# sbus-inverter-pro-micro.net
KiCad netlist of a schematic drawn in EAGLE
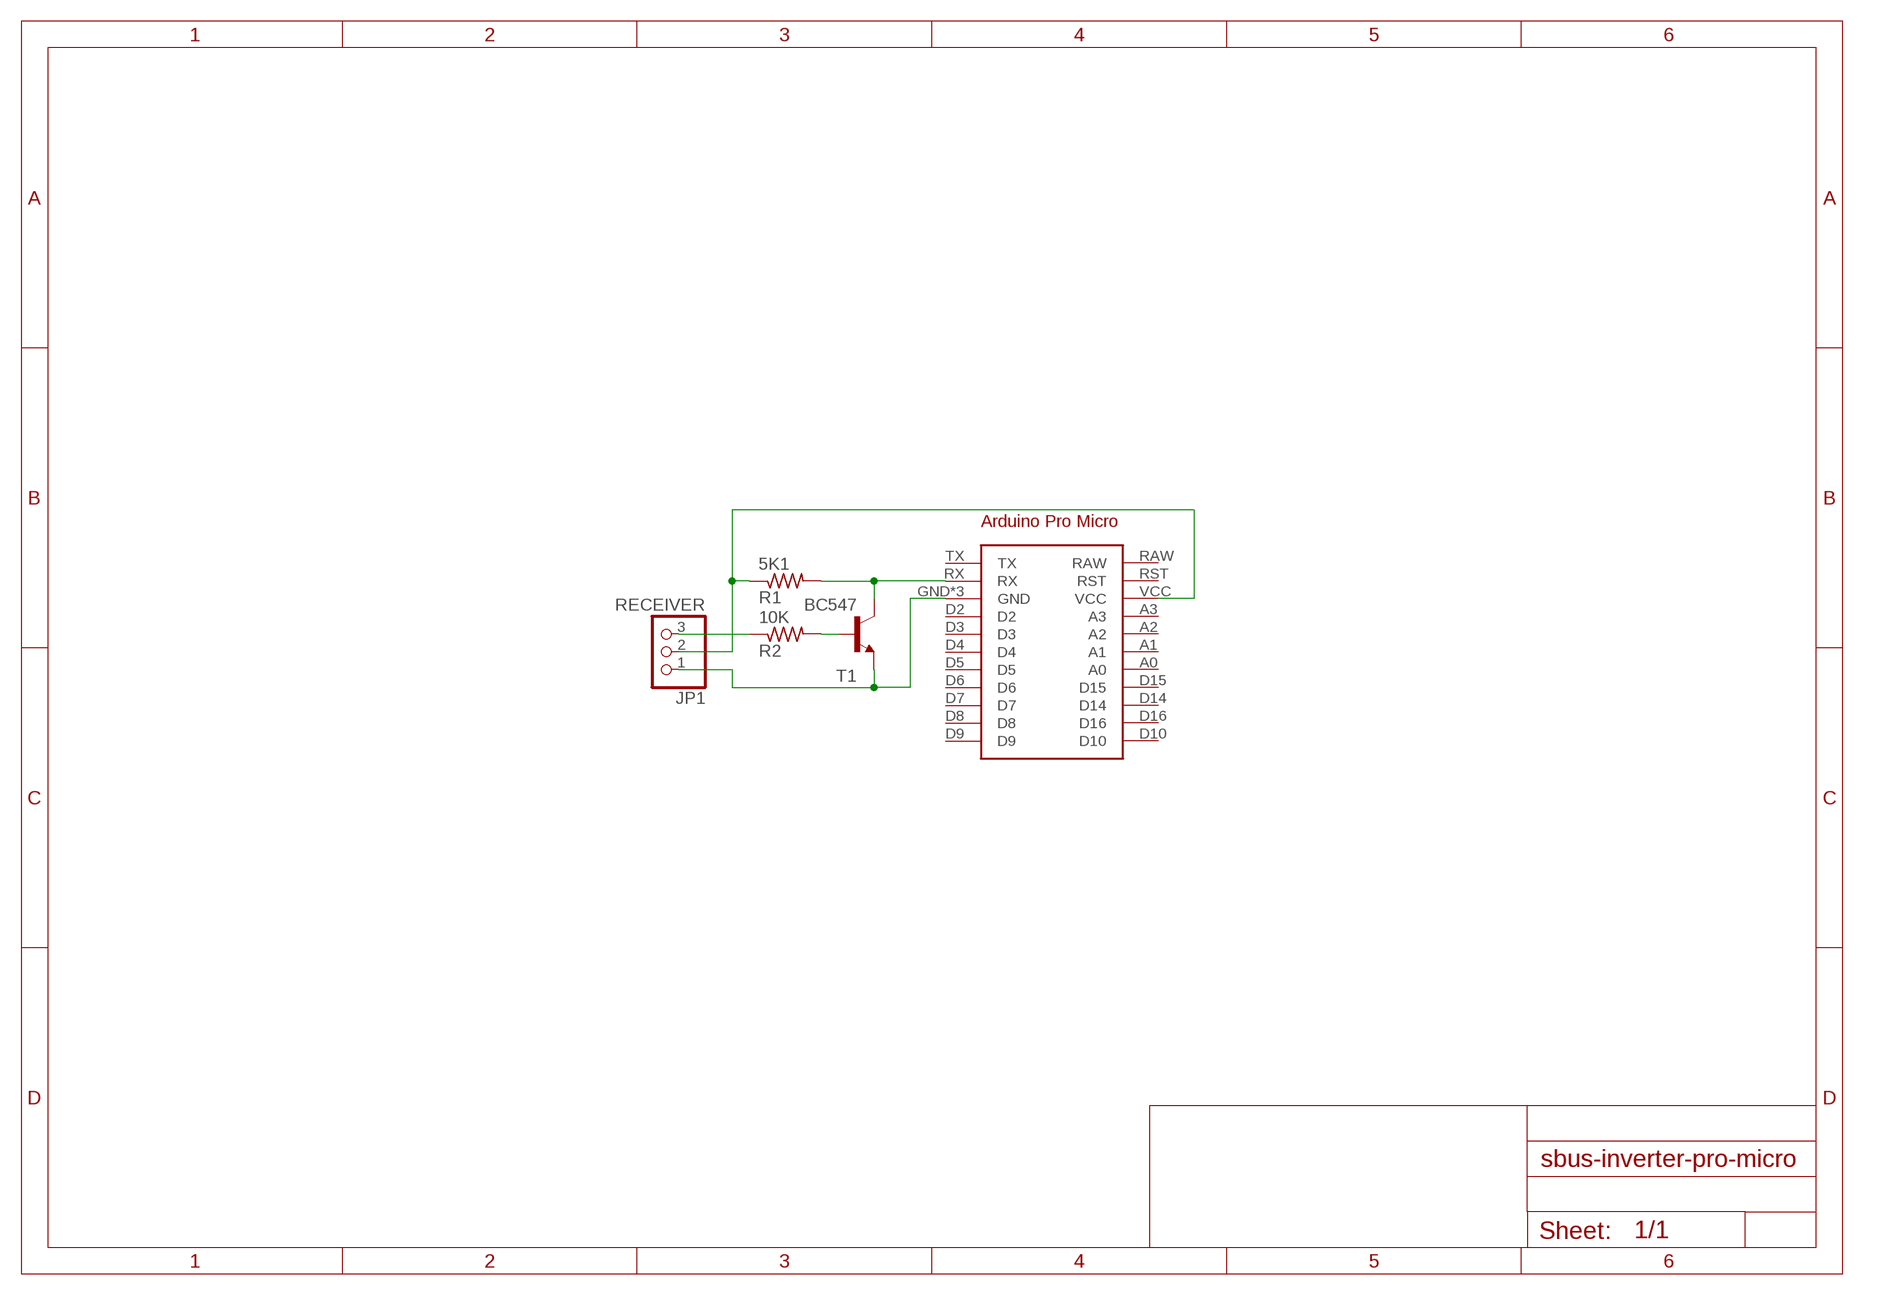
[diagram p0: schematic, sheet 1]

(export (version "E")
  (design (tool "Eeschema 10.0.6"))
  (components
    (comp (ref "ARDUINO1")
      (value "ARDUINO_PRO_MICRO")
      (footprint "eagle-import:ARDUINO_PRO_MICRO")
      (libsource (lib "eagle-import") (part "ARDUINO_PRO_MICRO"))
    )
    (comp (ref "JP1")
      (value "RECEIVER")
      (footprint "eagle-import:1X03_90")
      (libsource (lib "eagle-import") (part "PINHD-1X3/90"))
    )
    (comp (ref "R1")
      (value "5K1")
      (footprint "eagle-import:0207_10")
      (libsource (lib "eagle-import") (part "R-US_0207/10"))
    )
    (comp (ref "R2")
      (value "10K")
      (footprint "eagle-import:0207_10")
      (libsource (lib "eagle-import") (part "R-US_0207/10"))
    )
    (comp (ref "T1")
      (value "BC547")
      (footprint "eagle-import:TO92")
      (libsource (lib "eagle-import") (part "BC547"))
    )
  )
  (nets
    (net (code "1") (name "Net-(ARDUINO1-PadVCC)") (class "Default")
      (node (ref "ARDUINO1") (pin "VCC") (pinfunction "VCC_VCC") (pintype "power_in"))
      (node (ref "JP1") (pin "2") (pinfunction "2_2") (pintype "passive"))
      (node (ref "R1") (pin "1") (pinfunction "1_1") (pintype "passive"))
    )
    (net (code "2") (name "Net-(JP1-Pad3)") (class "Default")
      (node (ref "JP1") (pin "3") (pinfunction "3_3") (pintype "passive"))
      (node (ref "R2") (pin "1") (pinfunction "1_1") (pintype "passive"))
    )
    (net (code "3") (name "Net-(T1-B)") (class "Default")
      (node (ref "R2") (pin "2") (pinfunction "2_2") (pintype "passive"))
      (node (ref "T1") (pin "2") (pinfunction "B_2") (pintype "passive"))
    )
    (net (code "4") (name "Net-(T1-C)") (class "Default")
      (node (ref "ARDUINO1") (pin "RX") (pinfunction "RX_RX") (pintype "bidirectional"))
      (node (ref "R1") (pin "2") (pinfunction "2_2") (pintype "passive"))
      (node (ref "T1") (pin "3") (pinfunction "C_3") (pintype "passive"))
    )
    (net (code "5") (name "Net-(T1-E)") (class "Default")
      (node (ref "ARDUINO1") (pin "GND") (pinfunction "GND_GND") (pintype "power_in"))
      (node (ref "ARDUINO1") (pin "GND@1") (pinfunction "GND_GND@1") (pintype "power_in"))
      (node (ref "ARDUINO1") (pin "GND@2") (pinfunction "GND_GND@2") (pintype "power_in"))
      (node (ref "JP1") (pin "1") (pinfunction "1_1") (pintype "passive"))
      (node (ref "T1") (pin "1") (pinfunction "E_1") (pintype "passive"))
    )
    (net (code "6") (name "unconnected-(ARDUINO1-PadA0)") (class "Default")
      (node (ref "ARDUINO1") (pin "A0") (pinfunction "A0_A0") (pintype "bidirectional"))
    )
    (net (code "7") (name "unconnected-(ARDUINO1-PadA1)") (class "Default")
      (node (ref "ARDUINO1") (pin "A1") (pinfunction "A1_A1") (pintype "bidirectional"))
    )
    (net (code "8") (name "unconnected-(ARDUINO1-PadA2)") (class "Default")
      (node (ref "ARDUINO1") (pin "A2") (pinfunction "A2_A2") (pintype "bidirectional"))
    )
    (net (code "9") (name "unconnected-(ARDUINO1-PadA3)") (class "Default")
      (node (ref "ARDUINO1") (pin "A3") (pinfunction "A3_A3") (pintype "bidirectional"))
    )
    (net (code "10") (name "unconnected-(ARDUINO1-PadD2)") (class "Default")
      (node (ref "ARDUINO1") (pin "D2") (pinfunction "D2_D2") (pintype "bidirectional"))
    )
    (net (code "11") (name "unconnected-(ARDUINO1-PadD3)") (class "Default")
      (node (ref "ARDUINO1") (pin "D3") (pinfunction "D3_D3") (pintype "bidirectional"))
    )
    (net (code "12") (name "unconnected-(ARDUINO1-PadD4)") (class "Default")
      (node (ref "ARDUINO1") (pin "D4") (pinfunction "D4_D4") (pintype "bidirectional"))
    )
    (net (code "13") (name "unconnected-(ARDUINO1-PadD5)") (class "Default")
      (node (ref "ARDUINO1") (pin "D5") (pinfunction "D5_D5") (pintype "bidirectional"))
    )
    (net (code "14") (name "unconnected-(ARDUINO1-PadD6)") (class "Default")
      (node (ref "ARDUINO1") (pin "D6") (pinfunction "D6_D6") (pintype "bidirectional"))
    )
    (net (code "15") (name "unconnected-(ARDUINO1-PadD7)") (class "Default")
      (node (ref "ARDUINO1") (pin "D7") (pinfunction "D7_D7") (pintype "bidirectional"))
    )
    (net (code "16") (name "unconnected-(ARDUINO1-PadD8)") (class "Default")
      (node (ref "ARDUINO1") (pin "D8") (pinfunction "D8_D8") (pintype "bidirectional"))
    )
    (net (code "17") (name "unconnected-(ARDUINO1-PadD9)") (class "Default")
      (node (ref "ARDUINO1") (pin "D9") (pinfunction "D9_D9") (pintype "bidirectional"))
    )
    (net (code "18") (name "unconnected-(ARDUINO1-PadD10)") (class "Default")
      (node (ref "ARDUINO1") (pin "D10") (pinfunction "D10_D10") (pintype "bidirectional"))
    )
    (net (code "19") (name "unconnected-(ARDUINO1-PadD14)") (class "Default")
      (node (ref "ARDUINO1") (pin "D14") (pinfunction "D14_D14") (pintype "bidirectional"))
    )
    (net (code "20") (name "unconnected-(ARDUINO1-PadD15)") (class "Default")
      (node (ref "ARDUINO1") (pin "D15") (pinfunction "D15_D15") (pintype "bidirectional"))
    )
    (net (code "21") (name "unconnected-(ARDUINO1-PadD16)") (class "Default")
      (node (ref "ARDUINO1") (pin "D16") (pinfunction "D16_D16") (pintype "bidirectional"))
    )
    (net (code "22") (name "unconnected-(ARDUINO1-PadRAW)") (class "Default")
      (node (ref "ARDUINO1") (pin "RAW") (pinfunction "RAW_RAW") (pintype "bidirectional"))
    )
    (net (code "23") (name "unconnected-(ARDUINO1-PadRST)") (class "Default")
      (node (ref "ARDUINO1") (pin "RST") (pinfunction "RST_RST") (pintype "bidirectional"))
    )
    (net (code "24") (name "unconnected-(ARDUINO1-PadTX)") (class "Default")
      (node (ref "ARDUINO1") (pin "TX") (pinfunction "TX_TX") (pintype "bidirectional"))
    )
  )
)
